# 3_mcu_radio_0.net
KiCad netlist of a schematic drawn in Altium Designer
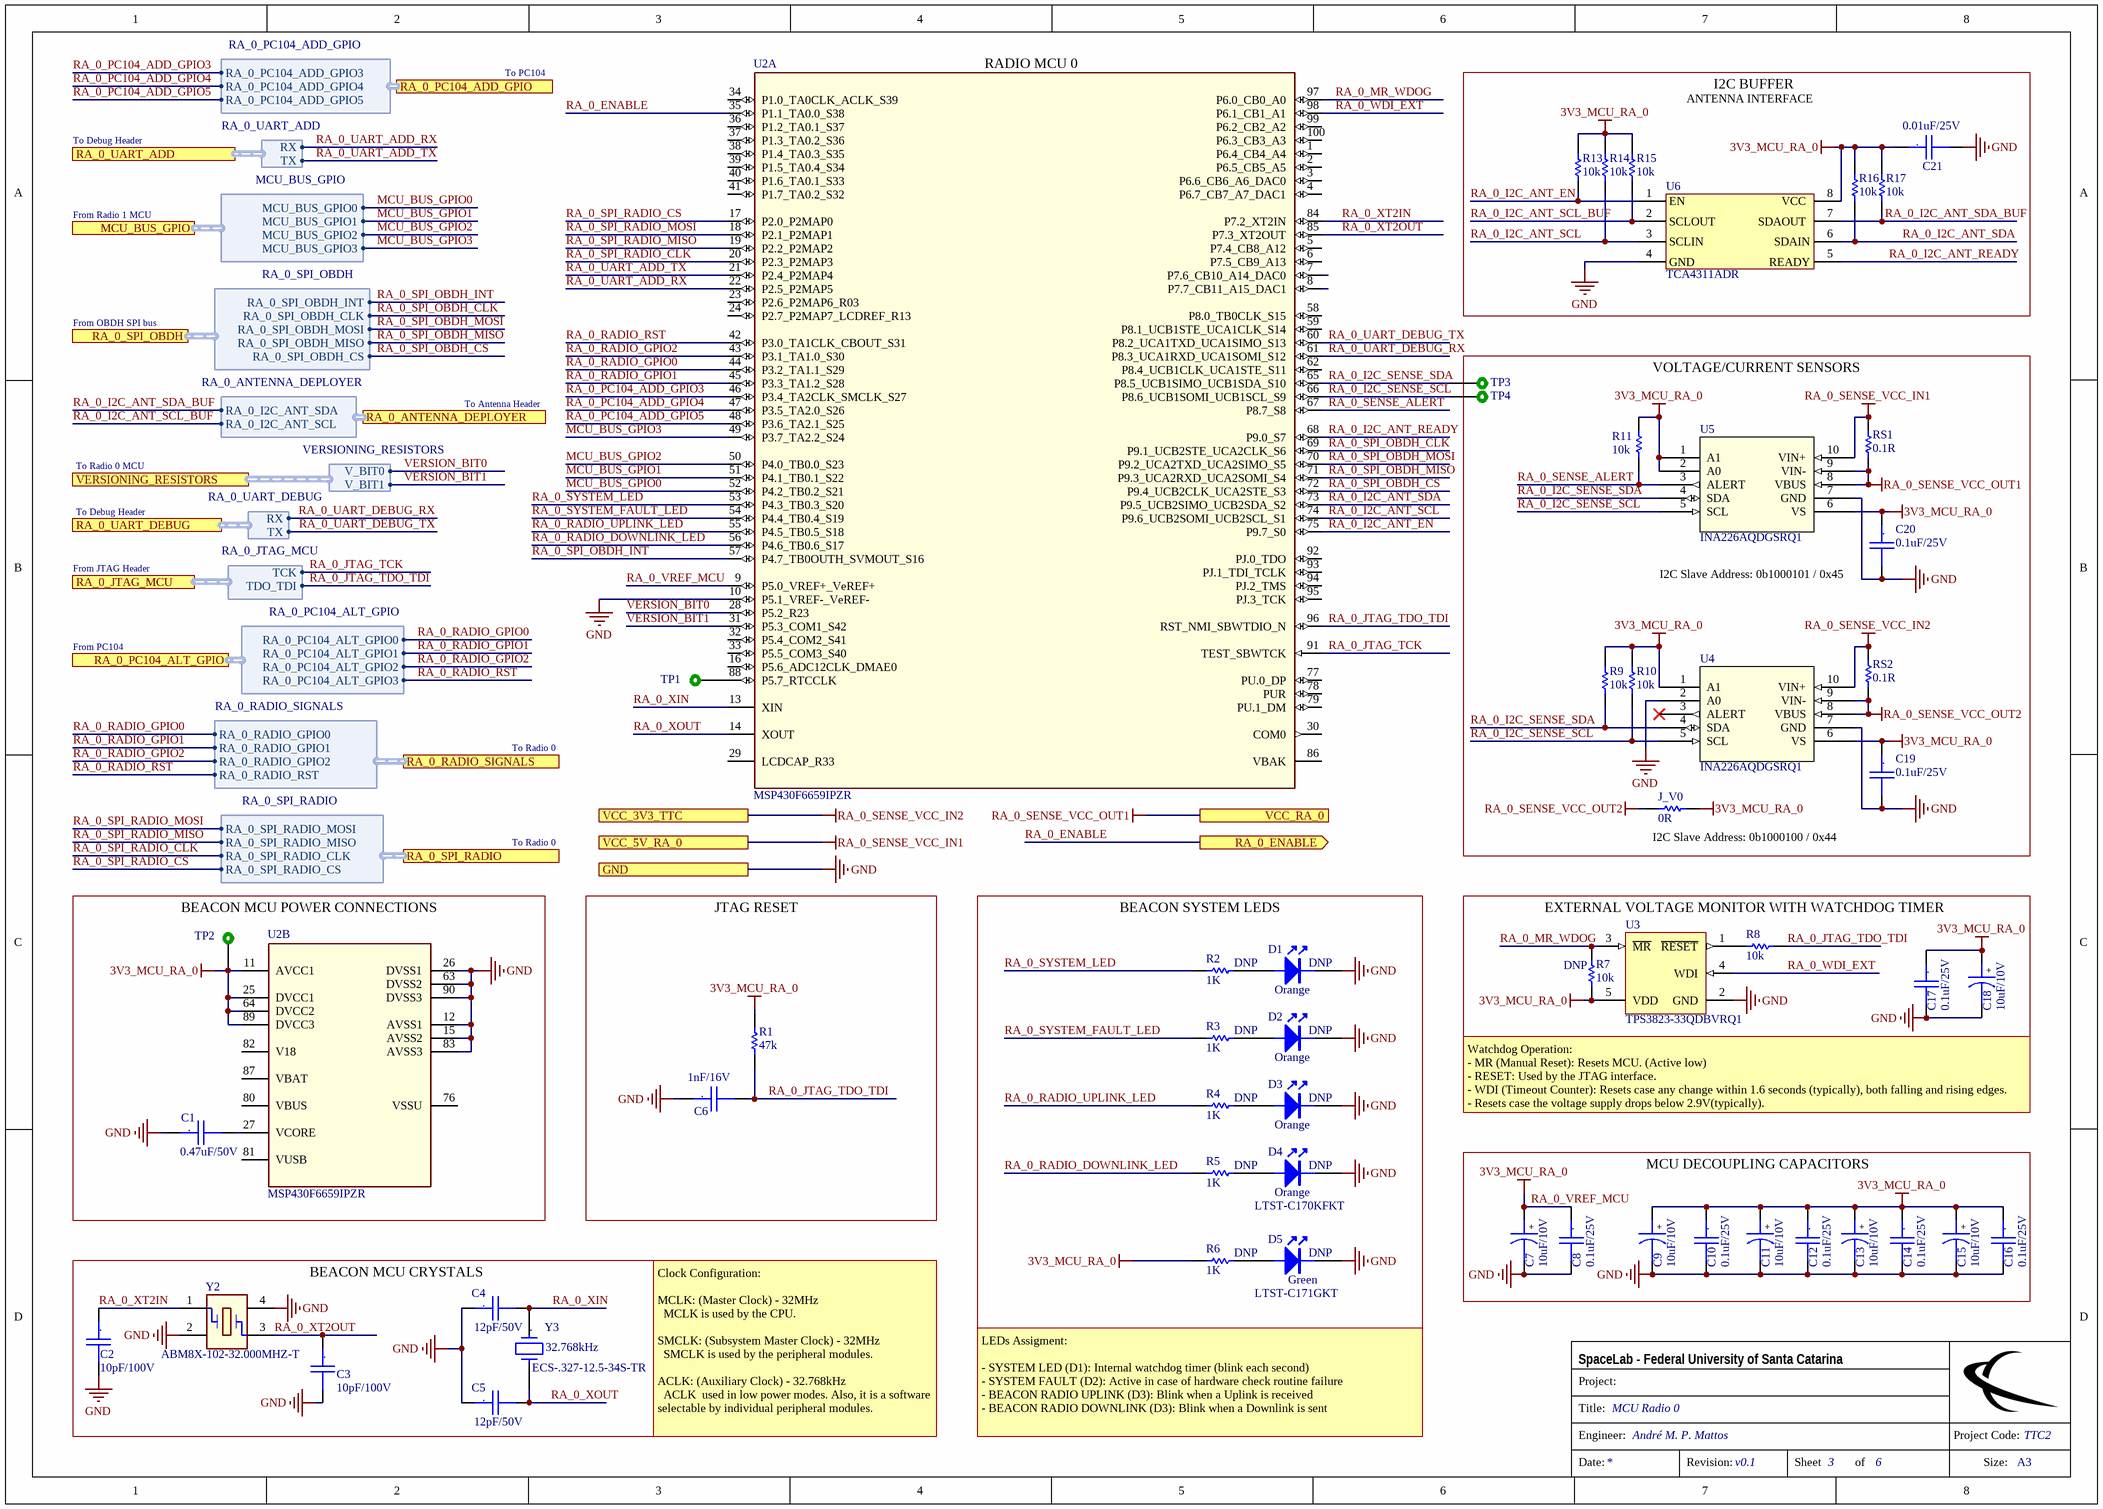
[diagram p0: 3_mcu_radio_0.schdoc]

(export (version "E")
  (design (tool "Eeschema 10.0.6"))
  (components
    (comp (ref "C1")
      (value "0.47uF/50V")
      (footprint "CC0805")
      (description "CAP CER 0.47UF 50V 10% X7R 0805")
      (fields (field (name "PARTNUMBER") "C0805C474K5RACTU"))
      (libsource (lib "schematics_library_legacy") (part "Cap_Cer_X7R_0.47uF_50V_0805"))
    )
    (comp (ref "C2")
      (value "10pF/100V")
      (footprint "CC0805")
      (description "CAP CER 10pF 100V 0805")
      (fields (field (name "PARTNUMBER") "08051A100FAT2A"))
      (libsource (lib "schematics_library_legacy") (part "Cap_Cer_X7R_10pF_100V_0805"))
    )
    (comp (ref "C3")
      (value "10pF/100V")
      (footprint "CC0805")
      (description "CAP CER 10pF 100V 0805")
      (fields (field (name "PARTNUMBER") "08051A100FAT2A"))
      (libsource (lib "schematics_library_legacy") (part "Cap_Cer_X7R_10pF_100V_0805"))
    )
    (comp (ref "C4")
      (value "12pF/50V")
      (footprint "CC0805")
      (description "CAP CER 12pF 50V 0805")
      (fields (field (name "PARTNUMBER") "CL21C120FBANNNC"))
      (libsource (lib "schematics_library_legacy") (part "Cap_Cer_X7R_12pF_50V_0805"))
    )
    (comp (ref "C5")
      (value "12pF/50V")
      (footprint "CC0805")
      (description "CAP CER 12pF 50V 0805")
      (fields (field (name "PARTNUMBER") "CL21C120FBANNNC"))
      (libsource (lib "schematics_library_legacy") (part "Cap_Cer_X7R_12pF_50V_0805"))
    )
    (comp (ref "C6")
      (value "1nF/16V")
      (footprint "CC0603")
      (description "CAP CER 1nF 16V 0603 5%")
      (fields (field (name "PARTNUMBER") "C0603X102J4RECAUTO"))
      (libsource (lib "schematics_library_legacy") (part "Cap_Cer_X7R_1nF_16V_0603"))
    )
    (comp (ref "C7")
      (value "10uF/10V")
      (footprint "CC0805_Tantalum")
      (description "CAP Tantalum 10uF 10V 20% 0805")
      (fields (field (name "PARTNUMBER") "TPSP106M010R2000"))
      (libsource (lib "schematics_library_legacy") (part "Cap_Tant_SMD_10uF_10V_0805"))
    )
    (comp (ref "C8")
      (value "0.1uF/25V")
      (footprint "CC0805")
      (description "CAP CER 0.1UF 25V 10% X7R 0805")
      (fields (field (name "PARTNUMBER") "CC0805KRX7R8BB104"))
      (libsource (lib "schematics_library_legacy") (part "Cap_Cer_X7R_0.1uF_25V_0805"))
    )
    (comp (ref "C9")
      (value "10uF/10V")
      (footprint "CC0805_Tantalum")
      (description "CAP Tantalum 10uF 10V 20% 0805")
      (fields (field (name "PARTNUMBER") "TPSP106M010R2000"))
      (libsource (lib "schematics_library_legacy") (part "Cap_Tant_SMD_10uF_10V_0805"))
    )
    (comp (ref "C10")
      (value "0.1uF/25V")
      (footprint "CC0805")
      (description "CAP CER 0.1UF 25V 10% X7R 0805")
      (fields (field (name "PARTNUMBER") "CC0805KRX7R8BB104"))
      (libsource (lib "schematics_library_legacy") (part "Cap_Cer_X7R_0.1uF_25V_0805"))
    )
    (comp (ref "C11")
      (value "10uF/10V")
      (footprint "CC0805_Tantalum")
      (description "CAP Tantalum 10uF 10V 20% 0805")
      (fields (field (name "PARTNUMBER") "TPSP106M010R2000"))
      (libsource (lib "schematics_library_legacy") (part "Cap_Tant_SMD_10uF_10V_0805"))
    )
    (comp (ref "C12")
      (value "0.1uF/25V")
      (footprint "CC0805")
      (description "CAP CER 0.1UF 25V 10% X7R 0805")
      (fields (field (name "PARTNUMBER") "CC0805KRX7R8BB104"))
      (libsource (lib "schematics_library_legacy") (part "Cap_Cer_X7R_0.1uF_25V_0805"))
    )
    (comp (ref "C13")
      (value "10uF/10V")
      (footprint "CC0805_Tantalum")
      (description "CAP Tantalum 10uF 10V 20% 0805")
      (fields (field (name "PARTNUMBER") "TPSP106M010R2000"))
      (libsource (lib "schematics_library_legacy") (part "Cap_Tant_SMD_10uF_10V_0805"))
    )
    (comp (ref "C14")
      (value "0.1uF/25V")
      (footprint "CC0805")
      (description "CAP CER 0.1UF 25V 10% X7R 0805")
      (fields (field (name "PARTNUMBER") "CC0805KRX7R8BB104"))
      (libsource (lib "schematics_library_legacy") (part "Cap_Cer_X7R_0.1uF_25V_0805"))
    )
    (comp (ref "C15")
      (value "10uF/10V")
      (footprint "CC0805_Tantalum")
      (description "CAP Tantalum 10uF 10V 20% 0805")
      (fields (field (name "PARTNUMBER") "TPSP106M010R2000"))
      (libsource (lib "schematics_library_legacy") (part "Cap_Tant_SMD_10uF_10V_0805"))
    )
    (comp (ref "C16")
      (value "0.1uF/25V")
      (footprint "CC0805")
      (description "CAP CER 0.1UF 25V 10% X7R 0805")
      (fields (field (name "PARTNUMBER") "CC0805KRX7R8BB104"))
      (libsource (lib "schematics_library_legacy") (part "Cap_Cer_X7R_0.1uF_25V_0805"))
    )
    (comp (ref "C17")
      (value "0.1uF/25V")
      (footprint "CC0805")
      (description "CAP CER 0.1UF 25V 10% X7R 0805")
      (fields (field (name "PARTNUMBER") "CC0805KRX7R8BB104"))
      (libsource (lib "schematics_library_legacy") (part "Cap_Cer_X7R_0.1uF_25V_0805"))
    )
    (comp (ref "C18")
      (value "10uF/10V")
      (footprint "CC0805_Tantalum")
      (description "CAP Tantalum 10uF 10V 20% 0805")
      (fields (field (name "PARTNUMBER") "TPSP106M010R2000"))
      (libsource (lib "schematics_library_legacy") (part "Cap_Tant_SMD_10uF_10V_0805"))
    )
    (comp (ref "C19")
      (value "0.1uF/25V")
      (footprint "CC0805")
      (description "CAP CER 0.1UF 25V 10% X7R 0805")
      (fields (field (name "PARTNUMBER") "CC0805KRX7R8BB104"))
      (libsource (lib "schematics_library_legacy") (part "Cap_Cer_X7R_0.1uF_25V_0805"))
    )
    (comp (ref "C20")
      (value "0.1uF/25V")
      (footprint "CC0805")
      (description "CAP CER 0.1UF 25V 10% X7R 0805")
      (fields (field (name "PARTNUMBER") "CC0805KRX7R8BB104"))
      (libsource (lib "schematics_library_legacy") (part "Cap_Cer_X7R_0.1uF_25V_0805"))
    )
    (comp (ref "C21")
      (value "0.01uF/25V")
      (footprint "CC0805")
      (description "CAP CER 0.01uF 25V 10% X7R 0805")
      (fields (field (name "PARTNUMBER") "CL21B103KAANNNC"))
      (libsource (lib "schematics_library_legacy") (part "Cap_Cer_X7R_0.01uF_25V_0805"))
    )
    (comp (ref "D1")
      (value "LTST-C170KFKT")
      (footprint "0805-ORANGE-LED")
      (description "LED Orange SMD - Orange 605nm LED Indication - Discrete 2V 0805 (2012 Metric)")
      (libsource (lib "schematics_library_legacy") (part "LED/O_0805"))
    )
    (comp (ref "D2")
      (value "LTST-C170KFKT")
      (footprint "0805-ORANGE-LED")
      (description "LED Orange SMD - Orange 605nm LED Indication - Discrete 2V 0805 (2012 Metric)")
      (libsource (lib "schematics_library_legacy") (part "LED/O_0805"))
    )
    (comp (ref "D3")
      (value "LTST-C170KFKT")
      (footprint "0805-ORANGE-LED")
      (description "LED Orange SMD - Orange 605nm LED Indication - Discrete 2V 0805 (2012 Metric)")
      (libsource (lib "schematics_library_legacy") (part "LED/O_0805"))
    )
    (comp (ref "D4")
      (value "LTST-C170KFKT")
      (footprint "0805-ORANGE-LED")
      (description "LED Orange SMD - Orange 605nm LED Indication - Discrete 2V 0805 (2012 Metric)")
      (libsource (lib "schematics_library_legacy") (part "LED/O_0805"))
    )
    (comp (ref "D5")
      (value "LTST-C171GKT")
      (footprint "0805-GREEN-LED")
      (description "LED Green SMD - Green 569nm LED Indication - Discrete 2.1V 0805 (2012 Metric)")
      (libsource (lib "schematics_library_legacy") (part "LED/G_0805"))
    )
    (comp (ref "J_V0")
      (value "0R")
      (footprint "0805")
      (description "RES 0R OHM 1/8W JUMPER 0805")
      (fields (field (name "PARTNUMBER") "CRCW08050000Z0EA"))
      (libsource (lib "schematics_library_legacy") (part "R0R_JUMPER_1/8W_0805"))
    )
    (comp (ref "R1")
      (value "47k")
      (footprint "0805")
      (description "RES 47k OHM 1/8W 1% 0805")
      (fields (field (name "PARTNUMBER") "RC0805FR-0747KL"))
      (libsource (lib "schematics_library_legacy") (part "R47k_1%_1/8W_0805"))
    )
    (comp (ref "R2")
      (value "1K")
      (footprint "0805")
      (description "RES 1.0K OHM 1/8W 1% 0805")
      (fields (field (name "PARTNUMBER") "RC0805FR-071KL"))
      (libsource (lib "schematics_library_legacy") (part "R1.0k_1%_1/8W_0805"))
    )
    (comp (ref "R3")
      (value "1K")
      (footprint "0805")
      (description "RES 1.0K OHM 1/8W 1% 0805")
      (fields (field (name "PARTNUMBER") "RC0805FR-071KL"))
      (libsource (lib "schematics_library_legacy") (part "R1.0k_1%_1/8W_0805"))
    )
    (comp (ref "R4")
      (value "1K")
      (footprint "0805")
      (description "RES 1.0K OHM 1/8W 1% 0805")
      (fields (field (name "PARTNUMBER") "RC0805FR-071KL"))
      (libsource (lib "schematics_library_legacy") (part "R1.0k_1%_1/8W_0805"))
    )
    (comp (ref "R5")
      (value "1K")
      (footprint "0805")
      (description "RES 1.0K OHM 1/8W 1% 0805")
      (fields (field (name "PARTNUMBER") "RC0805FR-071KL"))
      (libsource (lib "schematics_library_legacy") (part "R1.0k_1%_1/8W_0805"))
    )
    (comp (ref "R6")
      (value "1K")
      (footprint "0805")
      (description "RES 1.0K OHM 1/8W 1% 0805")
      (fields (field (name "PARTNUMBER") "RC0805FR-071KL"))
      (libsource (lib "schematics_library_legacy") (part "R1.0k_1%_1/8W_0805"))
    )
    (comp (ref "R7")
      (value "10k")
      (footprint "0805")
      (description "RES 10K OHM 1/8W 1%  0805")
      (fields (field (name "PARTNUMBER") "CRCW080510K0FKEA"))
      (libsource (lib "schematics_library_legacy") (part "R10k_1%_1/8W_0805"))
    )
    (comp (ref "R8")
      (value "10k")
      (footprint "0805")
      (description "RES 10K OHM 1/8W 1%  0805")
      (fields (field (name "PARTNUMBER") "CRCW080510K0FKEA"))
      (libsource (lib "schematics_library_legacy") (part "R10k_1%_1/8W_0805"))
    )
    (comp (ref "R9")
      (value "10k")
      (footprint "0805")
      (description "RES 10K OHM 1/8W 1%  0805")
      (fields (field (name "PARTNUMBER") "CRCW080510K0FKEA"))
      (libsource (lib "schematics_library_legacy") (part "R10k_1%_1/8W_0805"))
    )
    (comp (ref "R10")
      (value "10k")
      (footprint "0805")
      (description "RES 10K OHM 1/8W 1%  0805")
      (fields (field (name "PARTNUMBER") "CRCW080510K0FKEA"))
      (libsource (lib "schematics_library_legacy") (part "R10k_1%_1/8W_0805"))
    )
    (comp (ref "R11")
      (value "10k")
      (footprint "0805")
      (description "RES 10K OHM 1/8W 1%  0805")
      (fields (field (name "PARTNUMBER") "CRCW080510K0FKEA"))
      (libsource (lib "schematics_library_legacy") (part "R10k_1%_1/8W_0805"))
    )
    (comp (ref "R13")
      (value "10k")
      (footprint "0805")
      (description "RES 10K OHM 1/8W 1%  0805")
      (fields (field (name "PARTNUMBER") "CRCW080510K0FKEA"))
      (libsource (lib "schematics_library_legacy") (part "R10k_1%_1/8W_0805"))
    )
    (comp (ref "R14")
      (value "10k")
      (footprint "0805")
      (description "RES 10K OHM 1/8W 1%  0805")
      (fields (field (name "PARTNUMBER") "CRCW080510K0FKEA"))
      (libsource (lib "schematics_library_legacy") (part "R10k_1%_1/8W_0805"))
    )
    (comp (ref "R15")
      (value "10k")
      (footprint "0805")
      (description "RES 10K OHM 1/8W 1%  0805")
      (fields (field (name "PARTNUMBER") "CRCW080510K0FKEA"))
      (libsource (lib "schematics_library_legacy") (part "R10k_1%_1/8W_0805"))
    )
    (comp (ref "R16")
      (value "10k")
      (footprint "0805")
      (description "RES 10K OHM 1/8W 1%  0805")
      (fields (field (name "PARTNUMBER") "CRCW080510K0FKEA"))
      (libsource (lib "schematics_library_legacy") (part "R10k_1%_1/8W_0805"))
    )
    (comp (ref "R17")
      (value "10k")
      (footprint "0805")
      (description "RES 10K OHM 1/8W 1%  0805")
      (fields (field (name "PARTNUMBER") "CRCW080510K0FKEA"))
      (libsource (lib "schematics_library_legacy") (part "R10k_1%_1/8W_0805"))
    )
    (comp (ref "RS1")
      (value "0.1R")
      (footprint "0805")
      (description "RES 0.1R OHM 1/3W 1% 0805")
      (fields (field (name "PARTNUMBER") "SR732ATTER100F"))
      (libsource (lib "schematics_library_legacy") (part "R0.1R_1%_1/3W_0805"))
    )
    (comp (ref "RS2")
      (value "0.1R")
      (footprint "0805")
      (description "RES 0.1R OHM 1/3W 1% 0805")
      (fields (field (name "PARTNUMBER") "SR732ATTER100F"))
      (libsource (lib "schematics_library_legacy") (part "R0.1R_1%_1/3W_0805"))
    )
    (comp (ref "TP1")
      (value "TEST_POINT")
      (footprint "TEST_POINT")
      (description "Test point")
      (libsource (lib "schematics_library_legacy") (part "TEST_POINT"))
    )
    (comp (ref "TP2")
      (value "TEST_POINT")
      (footprint "TEST_POINT")
      (description "Test point")
      (libsource (lib "schematics_library_legacy") (part "TEST_POINT"))
    )
    (comp (ref "TP3")
      (value "TEST_POINT")
      (footprint "TEST_POINT")
      (description "Test point")
      (libsource (lib "schematics_library_legacy") (part "TEST_POINT"))
    )
    (comp (ref "TP4")
      (value "TEST_POINT")
      (footprint "TEST_POINT")
      (description "Test point")
      (libsource (lib "schematics_library_legacy") (part "TEST_POINT"))
    )
    (comp (ref "U2")
      (value "MSP430F6659IPZR")
      (footprint "LQFP-100")
      (description "CPUXV2 series Microcontroller IC 16-Bit 20MHz 512KB (512K x 8) FLASH 100-LQFP (14x14)")
      (fields
        (field (name "ALTERNATE PARTNUMBER") "MSP430F6659IPZ")
        (field (name "MANUFACTURER") "Texas Instruments")
      )
      (libsource (lib "schematics_library_legacy") (part "MSP430F6659IPZR"))
    )
    (comp (ref "U3")
      (value "TPS3823-33QDBVRQ1")
      (footprint "DBV0005A_N")
      (fields (field (name "MANUFACTURER") "Texas Instruments"))
      (libsource (lib "schematics_library_legacy") (part "CMP-0338-00011-2"))
    )
    (comp (ref "U4")
      (value "INA226AQDGSRQ1")
      (footprint "DGS10")
      (description "High-Side Measurement, Bi-Directional Current/Power Monitor w/I2C Interface")
      (fields
        (field (name "MANUFACTURER") "Texas Instruments")
        (field (name "GENERIC_PART_NUMBER") "INA226")
        (field (name "COPYRIGHT") "Copyright (C) 2018 Accelerated Designs. All rights reserved")
      )
      (libsource (lib "schematics_library_legacy") (part "INA226AQDGSRQ1"))
    )
    (comp (ref "U5")
      (value "INA226AQDGSRQ1")
      (footprint "DGS10")
      (description "High-Side Measurement, Bi-Directional Current/Power Monitor w/I2C Interface")
      (fields
        (field (name "MANUFACTURER") "Texas Instruments")
        (field (name "GENERIC_PART_NUMBER") "INA226")
        (field (name "COPYRIGHT") "Copyright (C) 2018 Accelerated Designs. All rights reserved")
      )
      (libsource (lib "schematics_library_legacy") (part "INA226AQDGSRQ1"))
    )
    (comp (ref "U6")
      (value "TCA4311ADR")
      (footprint "SOIC8")
      (description "IC SIGNAL BUFFER I2C 8SOIC HOTSWAP")
      (libsource (lib "schematics_library_legacy") (part "TCA4311ADR"))
    )
    (comp (ref "Y2")
      (value "ABM8X-102-32.000MHZ-T")
      (footprint "XTAL_ABM8X")
      (description "32MHz ±10ppm Crystal 10pF 60 Ohm -40°C ~ 125°C")
      (libsource (lib "schematics_library_legacy") (part "XTAL_32MHz_SMD_4-SMD"))
    )
    (comp (ref "Y3")
      (value "ECS-.327-12.5-34S-TR")
      (footprint "ABS06 0805")
      (description "32.768kHz ±20ppm Crystal 12.5pF 70 kOhm -40°C ~ 125°C")
      (libsource (lib "schematics_library_legacy") (part "Xtal_32.768kHz_12pF_2_SMD"))
    )
  )
  (nets
    (net (code "13") (name "/MCU_BUS_GPIO0") (class "Default")
      (node (ref "U2") (pin "52") (pinfunction "P4.2_TB0.2_S21_52") (pintype "bidirectional"))
    )
    (net (code "14") (name "/MCU_BUS_GPIO1") (class "Default")
      (node (ref "U2") (pin "51") (pinfunction "P4.1_TB0.1_S22_51") (pintype "bidirectional"))
    )
    (net (code "15") (name "/MCU_BUS_GPIO2") (class "Default")
      (node (ref "U2") (pin "50") (pinfunction "P4.0_TB0.0_S23_50") (pintype "bidirectional"))
    )
    (net (code "16") (name "/MCU_BUS_GPIO3") (class "Default")
      (node (ref "U2") (pin "49") (pinfunction "P3.7_TA2.2_S24_49") (pintype "bidirectional"))
    )
    (net (code "17") (name "/RA_0_ENABLE") (class "Default")
      (node (ref "U2") (pin "35") (pinfunction "P1.1_TA0.0_S38_35") (pintype "bidirectional"))
    )
    (net (code "18") (name "/RA_0_I2C_ANT_EN") (class "Default")
      (node (ref "R13") (pin "1") (pinfunction "1_1") (pintype "passive"))
      (node (ref "U2") (pin "75") (pinfunction "P9.7_S0_75") (pintype "bidirectional"))
      (node (ref "U6") (pin "1") (pinfunction "EN_1") (pintype "passive"))
    )
    (net (code "19") (name "/RA_0_I2C_ANT_READY") (class "Default")
      (node (ref "U2") (pin "68") (pinfunction "P9.0_S7_68") (pintype "bidirectional"))
      (node (ref "U6") (pin "5") (pinfunction "READY_5") (pintype "passive"))
    )
    (net (code "20") (name "/RA_0_I2C_ANT_SCL") (class "Default")
      (node (ref "R14") (pin "1") (pinfunction "1_1") (pintype "passive"))
      (node (ref "U2") (pin "74") (pinfunction "P9.6_UCB2SOMI_UCB2SCL_S1_74") (pintype "bidirectional"))
      (node (ref "U6") (pin "3") (pinfunction "SCLIN_3") (pintype "passive"))
    )
    (net (code "21") (name "/RA_0_I2C_ANT_SCL_BUF") (class "Default")
      (node (ref "R15") (pin "1") (pinfunction "1_1") (pintype "passive"))
      (node (ref "U6") (pin "2") (pinfunction "SCLOUT_2") (pintype "passive"))
    )
    (net (code "22") (name "/RA_0_I2C_ANT_SDA") (class "Default")
      (node (ref "R16") (pin "1") (pinfunction "1_1") (pintype "passive"))
      (node (ref "U2") (pin "73") (pinfunction "P9.5_UCB2SIMO_UCB2SDA_S2_73") (pintype "bidirectional"))
      (node (ref "U6") (pin "6") (pinfunction "SDAIN_6") (pintype "passive"))
    )
    (net (code "23") (name "/RA_0_I2C_ANT_SDA_BUF") (class "Default")
      (node (ref "R17") (pin "1") (pinfunction "1_1") (pintype "passive"))
      (node (ref "U6") (pin "7") (pinfunction "SDAOUT_7") (pintype "passive"))
    )
    (net (code "24") (name "/RA_0_I2C_SENSE_SCL") (class "Default")
      (node (ref "R10") (pin "1") (pinfunction "1_1") (pintype "passive"))
      (node (ref "TP4") (pin "1") (pinfunction "1_1") (pintype "passive"))
      (node (ref "U2") (pin "66") (pinfunction "P8.6_UCB1SOMI_UCB1SCL_S9_66") (pintype "bidirectional"))
      (node (ref "U4") (pin "5") (pinfunction "SCL_5") (pintype "input"))
      (node (ref "U5") (pin "5") (pinfunction "SCL_5") (pintype "input"))
    )
    (net (code "25") (name "/RA_0_I2C_SENSE_SDA") (class "Default")
      (node (ref "R9") (pin "1") (pinfunction "1_1") (pintype "passive"))
      (node (ref "TP3") (pin "1") (pinfunction "1_1") (pintype "passive"))
      (node (ref "U2") (pin "65") (pinfunction "P8.5_UCB1SIMO_UCB1SDA_S10_65") (pintype "bidirectional"))
      (node (ref "U4") (pin "4") (pinfunction "SDA_4") (pintype "bidirectional"))
      (node (ref "U5") (pin "4") (pinfunction "SDA_4") (pintype "bidirectional"))
    )
    (net (code "26") (name "/RA_0_JTAG_TCK") (class "Default")
      (node (ref "U2") (pin "91") (pinfunction "TEST_SBWTCK_91") (pintype "input"))
    )
    (net (code "27") (name "/RA_0_JTAG_TDO_TDI") (class "Default")
      (node (ref "C6") (pin "2") (pinfunction "2_2") (pintype "passive"))
      (node (ref "R1") (pin "1") (pinfunction "1_1") (pintype "passive"))
      (node (ref "R8") (pin "1") (pinfunction "1_1") (pintype "passive"))
      (node (ref "U2") (pin "96") (pinfunction "RST_NMI_SBWTDIO_N_96") (pintype "bidirectional"))
    )
    (net (code "28") (name "/RA_0_MR_WDOG") (class "Default")
      (node (ref "R7") (pin "2") (pinfunction "2_2") (pintype "passive"))
      (node (ref "U2") (pin "97") (pinfunction "P6.0_CB0_A0_97") (pintype "bidirectional"))
      (node (ref "U3") (pin "3") (pinfunction "~{MR}_3") (pintype "input"))
    )
    (net (code "29") (name "/RA_0_PC104_ADD_GPIO3") (class "Default")
      (node (ref "U2") (pin "46") (pinfunction "P3.4_TA2CLK_SMCLK_S27_46") (pintype "bidirectional"))
    )
    (net (code "30") (name "/RA_0_PC104_ADD_GPIO4") (class "Default")
      (node (ref "U2") (pin "47") (pinfunction "P3.5_TA2.0_S26_47") (pintype "bidirectional"))
    )
    (net (code "31") (name "/RA_0_PC104_ADD_GPIO5") (class "Default")
      (node (ref "U2") (pin "48") (pinfunction "P3.6_TA2.1_S25_48") (pintype "bidirectional"))
    )
    (net (code "32") (name "/RA_0_RADIO_DOWNLINK_LED") (class "Default")
      (node (ref "R5") (pin "2") (pinfunction "2_2") (pintype "passive"))
      (node (ref "U2") (pin "56") (pinfunction "P4.6_TB0.6_S17_56") (pintype "bidirectional"))
    )
    (net (code "33") (name "/RA_0_RADIO_GPIO0") (class "Default")
      (node (ref "U2") (pin "44") (pinfunction "P3.2_TA1.1_S29_44") (pintype "bidirectional"))
    )
    (net (code "34") (name "/RA_0_RADIO_GPIO1") (class "Default")
      (node (ref "U2") (pin "45") (pinfunction "P3.3_TA1.2_S28_45") (pintype "bidirectional"))
    )
    (net (code "35") (name "/RA_0_RADIO_GPIO2") (class "Default")
      (node (ref "U2") (pin "43") (pinfunction "P3.1_TA1.0_S30_43") (pintype "bidirectional"))
    )
    (net (code "36") (name "/RA_0_RADIO_RST") (class "Default")
      (node (ref "U2") (pin "42") (pinfunction "P3.0_TA1CLK_CBOUT_S31_42") (pintype "bidirectional"))
    )
    (net (code "37") (name "/RA_0_RADIO_UPLINK_LED") (class "Default")
      (node (ref "R4") (pin "2") (pinfunction "2_2") (pintype "passive"))
      (node (ref "U2") (pin "55") (pinfunction "P4.5_TB0.5_S18_55") (pintype "bidirectional"))
    )
    (net (code "38") (name "/RA_0_SENSE_ALERT") (class "Default")
      (node (ref "R11") (pin "1") (pinfunction "1_1") (pintype "passive"))
      (node (ref "U2") (pin "67") (pinfunction "P8.7_S8_67") (pintype "bidirectional"))
      (node (ref "U5") (pin "3") (pinfunction "ALERT_3") (pintype "output"))
    )
    (net (code "39") (name "/RA_0_SPI_OBDH_CLK") (class "Default")
      (node (ref "U2") (pin "69") (pinfunction "P9.1_UCB2STE_UCA2CLK_S6_69") (pintype "bidirectional"))
    )
    (net (code "40") (name "/RA_0_SPI_OBDH_CS") (class "Default")
      (node (ref "U2") (pin "72") (pinfunction "P9.4_UCB2CLK_UCA2STE_S3_72") (pintype "bidirectional"))
    )
    (net (code "41") (name "/RA_0_SPI_OBDH_INT") (class "Default")
      (node (ref "U2") (pin "57") (pinfunction "P4.7_TB0OUTH_SVMOUT_S16_57") (pintype "bidirectional"))
    )
    (net (code "42") (name "/RA_0_SPI_OBDH_MISO") (class "Default")
      (node (ref "U2") (pin "71") (pinfunction "P9.3_UCA2RXD_UCA2SOMI_S4_71") (pintype "bidirectional"))
    )
    (net (code "43") (name "/RA_0_SPI_OBDH_MOSI") (class "Default")
      (node (ref "U2") (pin "70") (pinfunction "P9.2_UCA2TXD_UCA2SIMO_S5_70") (pintype "bidirectional"))
    )
    (net (code "44") (name "/RA_0_SPI_RADIO_CLK") (class "Default")
      (node (ref "U2") (pin "20") (pinfunction "P2.3_P2MAP3_20") (pintype "bidirectional"))
    )
    (net (code "45") (name "/RA_0_SPI_RADIO_CS") (class "Default")
      (node (ref "U2") (pin "17") (pinfunction "P2.0_P2MAP0_17") (pintype "bidirectional"))
    )
    (net (code "46") (name "/RA_0_SPI_RADIO_MISO") (class "Default")
      (node (ref "U2") (pin "19") (pinfunction "P2.2_P2MAP2_19") (pintype "bidirectional"))
    )
    (net (code "47") (name "/RA_0_SPI_RADIO_MOSI") (class "Default")
      (node (ref "U2") (pin "18") (pinfunction "P2.1_P2MAP1_18") (pintype "bidirectional"))
    )
    (net (code "48") (name "/RA_0_SYSTEM_FAULT_LED") (class "Default")
      (node (ref "R3") (pin "2") (pinfunction "2_2") (pintype "passive"))
      (node (ref "U2") (pin "54") (pinfunction "P4.4_TB0.4_S19_54") (pintype "bidirectional"))
    )
    (net (code "49") (name "/RA_0_SYSTEM_LED") (class "Default")
      (node (ref "R2") (pin "2") (pinfunction "2_2") (pintype "passive"))
      (node (ref "U2") (pin "53") (pinfunction "P4.3_TB0.3_S20_53") (pintype "bidirectional"))
    )
    (net (code "50") (name "/RA_0_UART_ADD_RX") (class "Default")
      (node (ref "U2") (pin "22") (pinfunction "P2.5_P2MAP5_22") (pintype "bidirectional"))
    )
    (net (code "51") (name "/RA_0_UART_ADD_TX") (class "Default")
      (node (ref "U2") (pin "21") (pinfunction "P2.4_P2MAP4_21") (pintype "bidirectional"))
    )
    (net (code "52") (name "/RA_0_UART_DEBUG_RX") (class "Default")
      (node (ref "U2") (pin "61") (pinfunction "P8.3_UCA1RXD_UCA1SOMI_S12_61") (pintype "bidirectional"))
    )
    (net (code "53") (name "/RA_0_UART_DEBUG_TX") (class "Default")
      (node (ref "U2") (pin "60") (pinfunction "P8.2_UCA1TXD_UCA1SIMO_S13_60") (pintype "bidirectional"))
    )
    (net (code "54") (name "/RA_0_WDI_EXT") (class "Default")
      (node (ref "U2") (pin "98") (pinfunction "P6.1_CB1_A1_98") (pintype "bidirectional"))
      (node (ref "U3") (pin "4") (pinfunction "WDI_4") (pintype "input"))
    )
    (net (code "55") (name "/RA_0_XIN") (class "Default")
      (node (ref "C4") (pin "2") (pinfunction "2_2") (pintype "passive"))
      (node (ref "U2") (pin "13") (pinfunction "XIN_13") (pintype "passive"))
      (node (ref "Y3") (pin "1") (pinfunction "1_1") (pintype "passive"))
    )
    (net (code "56") (name "/RA_0_XOUT") (class "Default")
      (node (ref "C5") (pin "2") (pinfunction "2_2") (pintype "passive"))
      (node (ref "U2") (pin "14") (pinfunction "XOUT_14") (pintype "passive"))
      (node (ref "Y3") (pin "2") (pinfunction "2_2") (pintype "passive"))
    )
    (net (code "57") (name "/RA_0_XT2IN") (class "Default")
      (node (ref "C2") (pin "1") (pinfunction "1_1") (pintype "passive"))
      (node (ref "U2") (pin "84") (pinfunction "P7.2_XT2IN_84") (pintype "bidirectional"))
      (node (ref "Y2") (pin "1") (pinfunction "1_1") (pintype "passive"))
    )
    (net (code "58") (name "/RA_0_XT2OUT") (class "Default")
      (node (ref "C3") (pin "1") (pinfunction "1_1") (pintype "passive"))
      (node (ref "U2") (pin "85") (pinfunction "P7.3_XT2OUT_85") (pintype "bidirectional"))
      (node (ref "Y2") (pin "3") (pinfunction "3_3") (pintype "passive"))
    )
    (net (code "59") (name "/VERSION_BIT0") (class "Default")
      (node (ref "U2") (pin "28") (pinfunction "P5.2_R23_28") (pintype "bidirectional"))
    )
    (net (code "60") (name "/VERSION_BIT1") (class "Default")
      (node (ref "U2") (pin "31") (pinfunction "P5.3_COM1_S42_31") (pintype "bidirectional"))
    )
    (net (code "72") (name "3V3_MCU_RA_0") (class "Default")
      (node (ref "C10") (pin "1") (pinfunction "1_1") (pintype "passive"))
      (node (ref "C11") (pin "1") (pinfunction "1_1") (pintype "passive"))
      (node (ref "C12") (pin "1") (pinfunction "1_1") (pintype "passive"))
      (node (ref "C13") (pin "1") (pinfunction "1_1") (pintype "passive"))
      (node (ref "C14") (pin "1") (pinfunction "1_1") (pintype "passive"))
      (node (ref "C15") (pin "1") (pinfunction "1_1") (pintype "passive"))
      (node (ref "C16") (pin "1") (pinfunction "1_1") (pintype "passive"))
      (node (ref "C17") (pin "1") (pinfunction "1_1") (pintype "passive"))
      (node (ref "C18") (pin "1") (pinfunction "1_1") (pintype "passive"))
      (node (ref "C19") (pin "1") (pinfunction "1_1") (pintype "passive"))
      (node (ref "C20") (pin "1") (pinfunction "1_1") (pintype "passive"))
      (node (ref "C21") (pin "1") (pinfunction "1_1") (pintype "passive"))
      (node (ref "C7") (pin "1") (pinfunction "1_1") (pintype "passive"))
      (node (ref "C8") (pin "1") (pinfunction "1_1") (pintype "passive"))
      (node (ref "C9") (pin "1") (pinfunction "1_1") (pintype "passive"))
      (node (ref "J_V0") (pin "1") (pinfunction "1_1") (pintype "passive"))
      (node (ref "R1") (pin "2") (pinfunction "2_2") (pintype "passive"))
      (node (ref "R10") (pin "2") (pinfunction "2_2") (pintype "passive"))
      (node (ref "R11") (pin "2") (pinfunction "2_2") (pintype "passive"))
      (node (ref "R13") (pin "2") (pinfunction "2_2") (pintype "passive"))
      (node (ref "R14") (pin "2") (pinfunction "2_2") (pintype "passive"))
      (node (ref "R15") (pin "2") (pinfunction "2_2") (pintype "passive"))
      (node (ref "R16") (pin "2") (pinfunction "2_2") (pintype "passive"))
      (node (ref "R17") (pin "2") (pinfunction "2_2") (pintype "passive"))
      (node (ref "R6") (pin "2") (pinfunction "2_2") (pintype "passive"))
      (node (ref "R7") (pin "1") (pinfunction "1_1") (pintype "passive"))
      (node (ref "R9") (pin "2") (pinfunction "2_2") (pintype "passive"))
      (node (ref "TP2") (pin "1") (pinfunction "1_1") (pintype "passive"))
      (node (ref "U2") (pin "11") (pinfunction "AVCC1_11") (pintype "power_in"))
      (node (ref "U2") (pin "25") (pinfunction "DVCC1_25") (pintype "power_in"))
      (node (ref "U2") (pin "64") (pinfunction "DVCC2_64") (pintype "power_in"))
      (node (ref "U2") (pin "89") (pinfunction "DVCC3_89") (pintype "power_in"))
      (node (ref "U2") (pin "9") (pinfunction "P5.0_VREF+_VeREF+_9") (pintype "bidirectional"))
      (node (ref "U3") (pin "5") (pinfunction "VDD_5") (pintype "power_in"))
      (node (ref "U4") (pin "1") (pinfunction "A1_1") (pintype "passive"))
      (node (ref "U4") (pin "6") (pinfunction "VS_6") (pintype "power_in"))
      (node (ref "U5") (pin "1") (pinfunction "A1_1") (pintype "passive"))
      (node (ref "U5") (pin "2") (pinfunction "A0_2") (pintype "passive"))
      (node (ref "U5") (pin "6") (pinfunction "VS_6") (pintype "power_in"))
      (node (ref "U6") (pin "8") (pinfunction "VCC_8") (pintype "power_in"))
    )
    (net (code "73") (name "GND") (class "Default")
      (node (ref "C1") (pin "1") (pinfunction "1_1") (pintype "passive"))
      (node (ref "C10") (pin "2") (pinfunction "2_2") (pintype "passive"))
      (node (ref "C11") (pin "2") (pinfunction "2_2") (pintype "passive"))
      (node (ref "C12") (pin "2") (pinfunction "2_2") (pintype "passive"))
      (node (ref "C13") (pin "2") (pinfunction "2_2") (pintype "passive"))
      (node (ref "C14") (pin "2") (pinfunction "2_2") (pintype "passive"))
      (node (ref "C15") (pin "2") (pinfunction "2_2") (pintype "passive"))
      (node (ref "C16") (pin "2") (pinfunction "2_2") (pintype "passive"))
      (node (ref "C17") (pin "2") (pinfunction "2_2") (pintype "passive"))
      (node (ref "C18") (pin "2") (pinfunction "2_2") (pintype "passive"))
      (node (ref "C19") (pin "2") (pinfunction "2_2") (pintype "passive"))
      (node (ref "C2") (pin "2") (pinfunction "2_2") (pintype "passive"))
      (node (ref "C20") (pin "2") (pinfunction "2_2") (pintype "passive"))
      (node (ref "C21") (pin "2") (pinfunction "2_2") (pintype "passive"))
      (node (ref "C3") (pin "2") (pinfunction "2_2") (pintype "passive"))
      (node (ref "C4") (pin "1") (pinfunction "1_1") (pintype "passive"))
      (node (ref "C5") (pin "1") (pinfunction "1_1") (pintype "passive"))
      (node (ref "C6") (pin "1") (pinfunction "1_1") (pintype "passive"))
      (node (ref "C7") (pin "2") (pinfunction "2_2") (pintype "passive"))
      (node (ref "C8") (pin "2") (pinfunction "2_2") (pintype "passive"))
      (node (ref "C9") (pin "2") (pinfunction "2_2") (pintype "passive"))
      (node (ref "D1") (pin "2") (pinfunction "K_2") (pintype "passive"))
      (node (ref "D2") (pin "2") (pinfunction "K_2") (pintype "passive"))
      (node (ref "D3") (pin "2") (pinfunction "K_2") (pintype "passive"))
      (node (ref "D4") (pin "2") (pinfunction "K_2") (pintype "passive"))
      (node (ref "D5") (pin "2") (pinfunction "K_2") (pintype "passive"))
      (node (ref "U2") (pin "10") (pinfunction "P5.1_VREF-_VeREF-_10") (pintype "bidirectional"))
      (node (ref "U2") (pin "12") (pinfunction "AVSS1_12") (pintype "power_in"))
      (node (ref "U2") (pin "15") (pinfunction "AVSS2_15") (pintype "power_in"))
      (node (ref "U2") (pin "26") (pinfunction "DVSS1_26") (pintype "passive"))
      (node (ref "U2") (pin "63") (pinfunction "DVSS2_63") (pintype "power_in"))
      (node (ref "U2") (pin "83") (pinfunction "AVSS3_83") (pintype "power_in"))
      (node (ref "U2") (pin "90") (pinfunction "DVSS3_90") (pintype "passive"))
      (node (ref "U3") (pin "2") (pinfunction "GND_2") (pintype "power_in"))
      (node (ref "U4") (pin "2") (pinfunction "A0_2") (pintype "passive"))
      (node (ref "U4") (pin "7") (pinfunction "GND_7") (pintype "power_in"))
      (node (ref "U5") (pin "7") (pinfunction "GND_7") (pintype "power_in"))
      (node (ref "U6") (pin "4") (pinfunction "GND_4") (pintype "passive"))
      (node (ref "Y2") (pin "2") (pinfunction "2_2") (pintype "passive"))
      (node (ref "Y2") (pin "4") (pinfunction "4_4") (pintype "passive"))
    )
    (net (code "74") (name "Net-(D1-A)") (class "Default")
      (node (ref "D1") (pin "1") (pinfunction "A_1") (pintype "passive"))
      (node (ref "R2") (pin "1") (pinfunction "1_1") (pintype "passive"))
    )
    (net (code "75") (name "Net-(D2-A)") (class "Default")
      (node (ref "D2") (pin "1") (pinfunction "A_1") (pintype "passive"))
      (node (ref "R3") (pin "1") (pinfunction "1_1") (pintype "passive"))
    )
    (net (code "76") (name "Net-(D3-A)") (class "Default")
      (node (ref "D3") (pin "1") (pinfunction "A_1") (pintype "passive"))
      (node (ref "R4") (pin "1") (pinfunction "1_1") (pintype "passive"))
    )
    (net (code "77") (name "Net-(D4-A)") (class "Default")
      (node (ref "D4") (pin "1") (pinfunction "A_1") (pintype "passive"))
      (node (ref "R5") (pin "1") (pinfunction "1_1") (pintype "passive"))
    )
    (net (code "78") (name "Net-(D5-A)") (class "Default")
      (node (ref "D5") (pin "1") (pinfunction "A_1") (pintype "passive"))
      (node (ref "R6") (pin "1") (pinfunction "1_1") (pintype "passive"))
    )
    (net (code "79") (name "Net-(U2A-P5.7_RTCCLK)") (class "Default")
      (node (ref "TP1") (pin "1") (pinfunction "1_1") (pintype "passive"))
      (node (ref "U2") (pin "88") (pinfunction "P5.7_RTCCLK_88") (pintype "bidirectional"))
    )
    (net (code "80") (name "Net-(U2B-VCORE)") (class "Default")
      (node (ref "C1") (pin "2") (pinfunction "2_2") (pintype "passive"))
      (node (ref "U2") (pin "27") (pinfunction "VCORE_27") (pintype "power_in"))
    )
    (net (code "81") (name "Net-(U3-~{RESET})") (class "Default")
      (node (ref "R8") (pin "2") (pinfunction "2_2") (pintype "passive"))
      (node (ref "U3") (pin "1") (pinfunction "~{RESET}_1") (pintype "output"))
    )
    (net (code "82") (name "RA_0_SENSE_VCC_IN1") (class "Default")
      (node (ref "RS1") (pin "2") (pinfunction "2_2") (pintype "passive"))
      (node (ref "U5") (pin "10") (pinfunction "VIN+_10") (pintype "input"))
    )
    (net (code "83") (name "RA_0_SENSE_VCC_IN2") (class "Default")
      (node (ref "RS2") (pin "2") (pinfunction "2_2") (pintype "passive"))
      (node (ref "U4") (pin "10") (pinfunction "VIN+_10") (pintype "input"))
    )
    (net (code "84") (name "RA_0_SENSE_VCC_OUT1") (class "Default")
      (node (ref "RS1") (pin "1") (pinfunction "1_1") (pintype "passive"))
      (node (ref "U5") (pin "8") (pinfunction "VBUS_8") (pintype "input"))
      (node (ref "U5") (pin "9") (pinfunction "VIN-_9") (pintype "input"))
    )
    (net (code "85") (name "RA_0_SENSE_VCC_OUT2") (class "Default")
      (node (ref "J_V0") (pin "2") (pinfunction "2_2") (pintype "passive"))
      (node (ref "RS2") (pin "1") (pinfunction "1_1") (pintype "passive"))
      (node (ref "U4") (pin "8") (pinfunction "VBUS_8") (pintype "input"))
      (node (ref "U4") (pin "9") (pinfunction "VIN-_9") (pintype "input"))
    )
    (net (code "86") (name "unconnected-(U2A-COM0-Pad30)") (class "Default")
      (node (ref "U2") (pin "30") (pinfunction "COM0_30") (pintype "output"))
    )
    (net (code "87") (name "unconnected-(U2A-LCDCAP_R33-Pad29)") (class "Default")
      (node (ref "U2") (pin "29") (pinfunction "LCDCAP_R33_29") (pintype "passive"))
    )
    (net (code "88") (name "unconnected-(U2A-P1.0_TA0CLK_ACLK_S39-Pad34)") (class "Default")
      (node (ref "U2") (pin "34") (pinfunction "P1.0_TA0CLK_ACLK_S39_34") (pintype "bidirectional"))
    )
    (net (code "89") (name "unconnected-(U2A-P1.2_TA0.1_S37-Pad36)") (class "Default")
      (node (ref "U2") (pin "36") (pinfunction "P1.2_TA0.1_S37_36") (pintype "bidirectional"))
    )
    (net (code "90") (name "unconnected-(U2A-P1.3_TA0.2_S36-Pad37)") (class "Default")
      (node (ref "U2") (pin "37") (pinfunction "P1.3_TA0.2_S36_37") (pintype "bidirectional"))
    )
    (net (code "91") (name "unconnected-(U2A-P1.4_TA0.3_S35-Pad38)") (class "Default")
      (node (ref "U2") (pin "38") (pinfunction "P1.4_TA0.3_S35_38") (pintype "bidirectional"))
    )
    (net (code "92") (name "unconnected-(U2A-P1.5_TA0.4_S34-Pad39)") (class "Default")
      (node (ref "U2") (pin "39") (pinfunction "P1.5_TA0.4_S34_39") (pintype "bidirectional"))
    )
    (net (code "93") (name "unconnected-(U2A-P1.6_TA0.1_S33-Pad40)") (class "Default")
      (node (ref "U2") (pin "40") (pinfunction "P1.6_TA0.1_S33_40") (pintype "bidirectional"))
    )
    (net (code "94") (name "unconnected-(U2A-P1.7_TA0.2_S32-Pad41)") (class "Default")
      (node (ref "U2") (pin "41") (pinfunction "P1.7_TA0.2_S32_41") (pintype "bidirectional"))
    )
    (net (code "95") (name "unconnected-(U2A-P2.6_P2MAP6_R03-Pad23)") (class "Default")
      (node (ref "U2") (pin "23") (pinfunction "P2.6_P2MAP6_R03_23") (pintype "bidirectional"))
    )
    (net (code "96") (name "unconnected-(U2A-P2.7_P2MAP7_LCDREF_R13-Pad24)") (class "Default")
      (node (ref "U2") (pin "24") (pinfunction "P2.7_P2MAP7_LCDREF_R13_24") (pintype "bidirectional"))
    )
    (net (code "97") (name "unconnected-(U2A-P5.4_COM2_S41-Pad32)") (class "Default")
      (node (ref "U2") (pin "32") (pinfunction "P5.4_COM2_S41_32") (pintype "bidirectional"))
    )
    (net (code "98") (name "unconnected-(U2A-P5.5_COM3_S40-Pad33)") (class "Default")
      (node (ref "U2") (pin "33") (pinfunction "P5.5_COM3_S40_33") (pintype "bidirectional"))
    )
    (net (code "99") (name "unconnected-(U2A-P5.6_ADC12CLK_DMAE0-Pad16)") (class "Default")
      (node (ref "U2") (pin "16") (pinfunction "P5.6_ADC12CLK_DMAE0_16") (pintype "bidirectional"))
    )
    (net (code "100") (name "unconnected-(U2A-P6.2_CB2_A2-Pad99)") (class "Default")
      (node (ref "U2") (pin "99") (pinfunction "P6.2_CB2_A2_99") (pintype "bidirectional"))
    )
    (net (code "101") (name "unconnected-(U2A-P6.3_CB3_A3-Pad100)") (class "Default")
      (node (ref "U2") (pin "100") (pinfunction "P6.3_CB3_A3_100") (pintype "bidirectional"))
    )
    (net (code "102") (name "unconnected-(U2A-P6.4_CB4_A4-Pad1)") (class "Default")
      (node (ref "U2") (pin "1") (pinfunction "P6.4_CB4_A4_1") (pintype "bidirectional"))
    )
    (net (code "103") (name "unconnected-(U2A-P6.5_CB5_A5-Pad2)") (class "Default")
      (node (ref "U2") (pin "2") (pinfunction "P6.5_CB5_A5_2") (pintype "bidirectional"))
    )
    (net (code "104") (name "unconnected-(U2A-P6.6_CB6_A6_DAC0-Pad3)") (class "Default")
      (node (ref "U2") (pin "3") (pinfunction "P6.6_CB6_A6_DAC0_3") (pintype "bidirectional"))
    )
    (net (code "105") (name "unconnected-(U2A-P6.7_CB7_A7_DAC1-Pad4)") (class "Default")
      (node (ref "U2") (pin "4") (pinfunction "P6.7_CB7_A7_DAC1_4") (pintype "bidirectional"))
    )
    (net (code "106") (name "unconnected-(U2A-P7.4_CB8_A12-Pad5)") (class "Default")
      (node (ref "U2") (pin "5") (pinfunction "P7.4_CB8_A12_5") (pintype "bidirectional"))
    )
    (net (code "107") (name "unconnected-(U2A-P7.5_CB9_A13-Pad6)") (class "Default")
      (node (ref "U2") (pin "6") (pinfunction "P7.5_CB9_A13_6") (pintype "bidirectional"))
    )
    (net (code "108") (name "unconnected-(U2A-P7.6_CB10_A14_DAC0-Pad7)") (class "Default")
      (node (ref "U2") (pin "7") (pinfunction "P7.6_CB10_A14_DAC0_7") (pintype "bidirectional"))
    )
    (net (code "109") (name "unconnected-(U2A-P7.7_CB11_A15_DAC1-Pad8)") (class "Default")
      (node (ref "U2") (pin "8") (pinfunction "P7.7_CB11_A15_DAC1_8") (pintype "bidirectional"))
    )
    (net (code "110") (name "unconnected-(U2A-P8.0_TB0CLK_S15-Pad58)") (class "Default")
      (node (ref "U2") (pin "58") (pinfunction "P8.0_TB0CLK_S15_58") (pintype "bidirectional"))
    )
    (net (code "111") (name "unconnected-(U2A-P8.1_UCB1STE_UCA1CLK_S14-Pad59)") (class "Default")
      (node (ref "U2") (pin "59") (pinfunction "P8.1_UCB1STE_UCA1CLK_S14_59") (pintype "bidirectional"))
    )
    (net (code "112") (name "unconnected-(U2A-P8.4_UCB1CLK_UCA1STE_S11-Pad62)") (class "Default")
      (node (ref "U2") (pin "62") (pinfunction "P8.4_UCB1CLK_UCA1STE_S11_62") (pintype "bidirectional"))
    )
    (net (code "113") (name "unconnected-(U2A-PJ.0_TDO-Pad92)") (class "Default")
      (node (ref "U2") (pin "92") (pinfunction "PJ.0_TDO_92") (pintype "bidirectional"))
    )
    (net (code "114") (name "unconnected-(U2A-PJ.1_TDI_TCLK-Pad93)") (class "Default")
      (node (ref "U2") (pin "93") (pinfunction "PJ.1_TDI_TCLK_93") (pintype "bidirectional"))
    )
    (net (code "115") (name "unconnected-(U2A-PJ.2_TMS-Pad94)") (class "Default")
      (node (ref "U2") (pin "94") (pinfunction "PJ.2_TMS_94") (pintype "bidirectional"))
    )
    (net (code "116") (name "unconnected-(U2A-PJ.3_TCK-Pad95)") (class "Default")
      (node (ref "U2") (pin "95") (pinfunction "PJ.3_TCK_95") (pintype "bidirectional"))
    )
    (net (code "117") (name "unconnected-(U2A-PU.0_DP-Pad77)") (class "Default")
      (node (ref "U2") (pin "77") (pinfunction "PU.0_DP_77") (pintype "bidirectional"))
    )
    (net (code "118") (name "unconnected-(U2A-PU.1_DM-Pad79)") (class "Default")
      (node (ref "U2") (pin "79") (pinfunction "PU.1_DM_79") (pintype "bidirectional"))
    )
    (net (code "119") (name "unconnected-(U2A-PUR-Pad78)") (class "Default")
      (node (ref "U2") (pin "78") (pinfunction "PUR_78") (pintype "bidirectional"))
    )
    (net (code "120") (name "unconnected-(U2A-VBAK-Pad86)") (class "Default")
      (node (ref "U2") (pin "86") (pinfunction "VBAK_86") (pintype "passive"))
    )
    (net (code "121") (name "unconnected-(U2B-V18-Pad82)") (class "Default")
      (node (ref "U2") (pin "82") (pinfunction "V18_82") (pintype "power_in"))
    )
    (net (code "122") (name "unconnected-(U2B-VBAT-Pad87)") (class "Default")
      (node (ref "U2") (pin "87") (pinfunction "VBAT_87") (pintype "power_in"))
    )
    (net (code "123") (name "unconnected-(U2B-VBUS-Pad80)") (class "Default")
      (node (ref "U2") (pin "80") (pinfunction "VBUS_80") (pintype "power_in"))
    )
    (net (code "124") (name "unconnected-(U2B-VSSU-Pad76)") (class "Default")
      (node (ref "U2") (pin "76") (pinfunction "VSSU_76") (pintype "power_in"))
    )
    (net (code "125") (name "unconnected-(U2B-VUSB-Pad81)") (class "Default")
      (node (ref "U2") (pin "81") (pinfunction "VUSB_81") (pintype "power_in"))
    )
    (net (code "126") (name "unconnected-(U4-ALERT-Pad3)") (class "Default")
      (node (ref "U4") (pin "3") (pinfunction "ALERT_3") (pintype "output+no_connect"))
    )
  )
)
